# 13-MT7688AN_Peripheral-C.net
KiCad netlist of a schematic drawn in Altium Designer
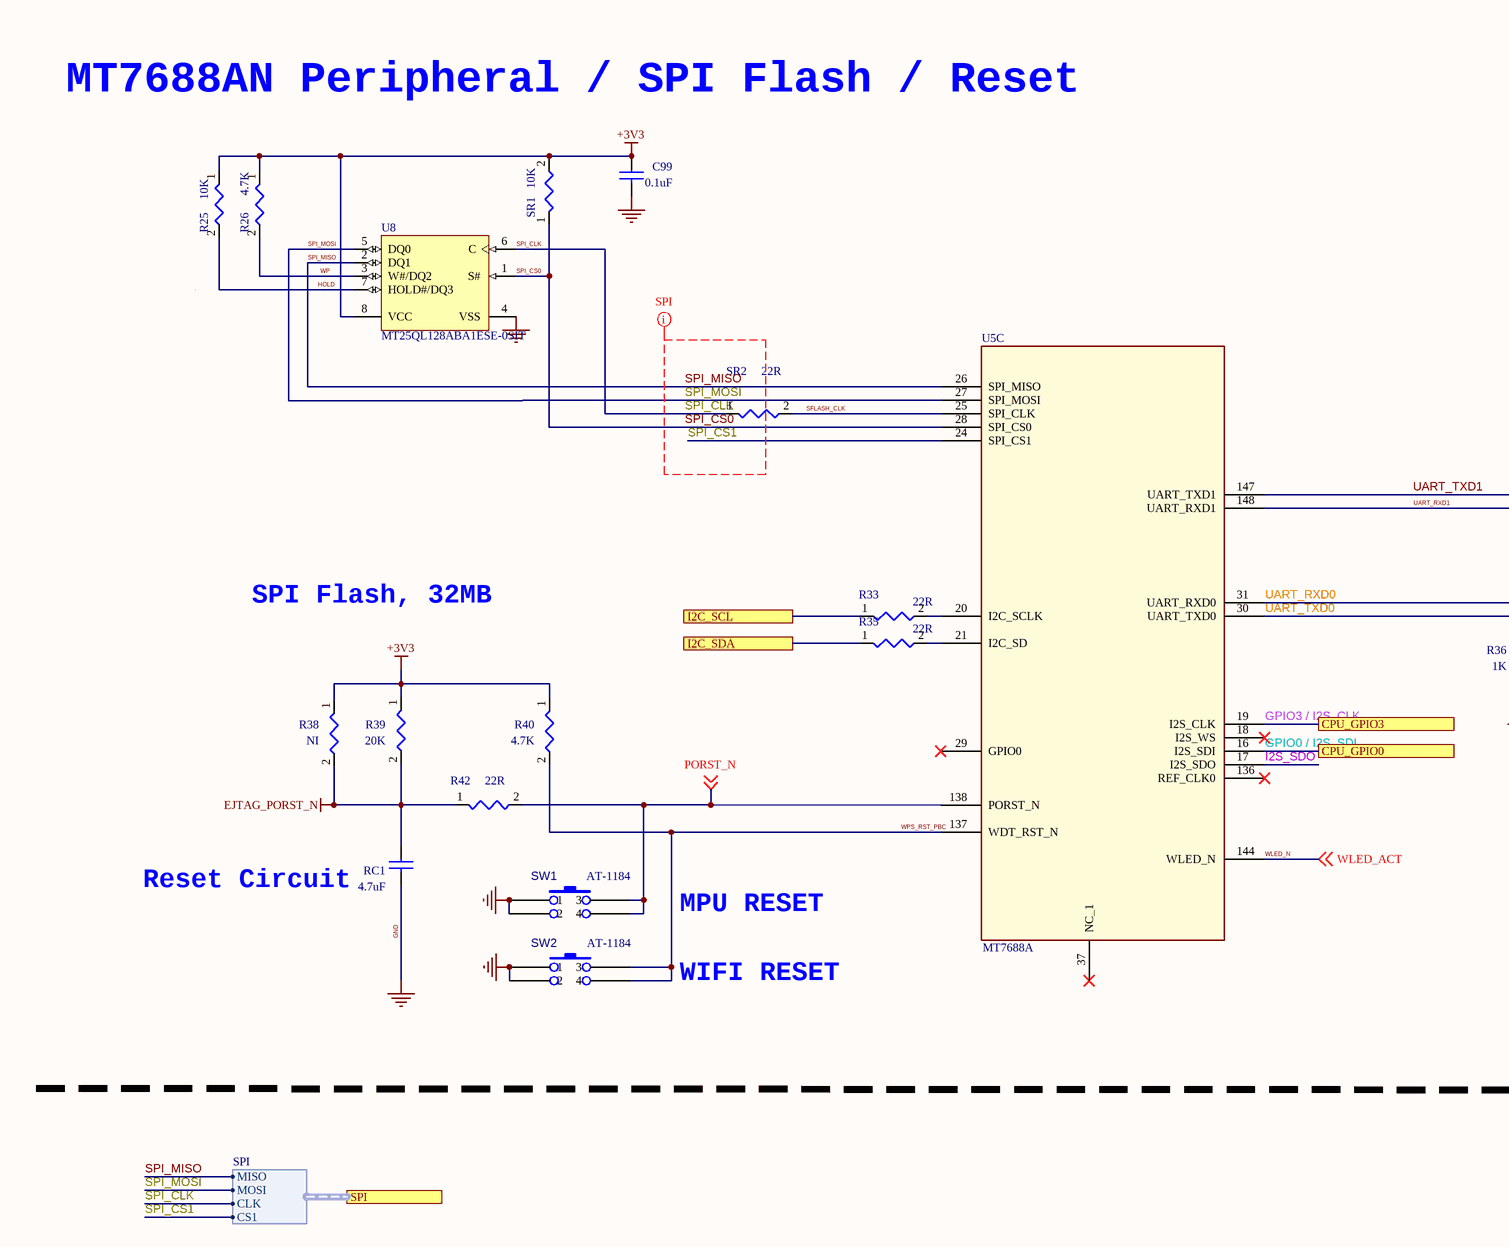
[diagram p0: 13-MT7688AN Peripheral-C.SchDoc, top left]
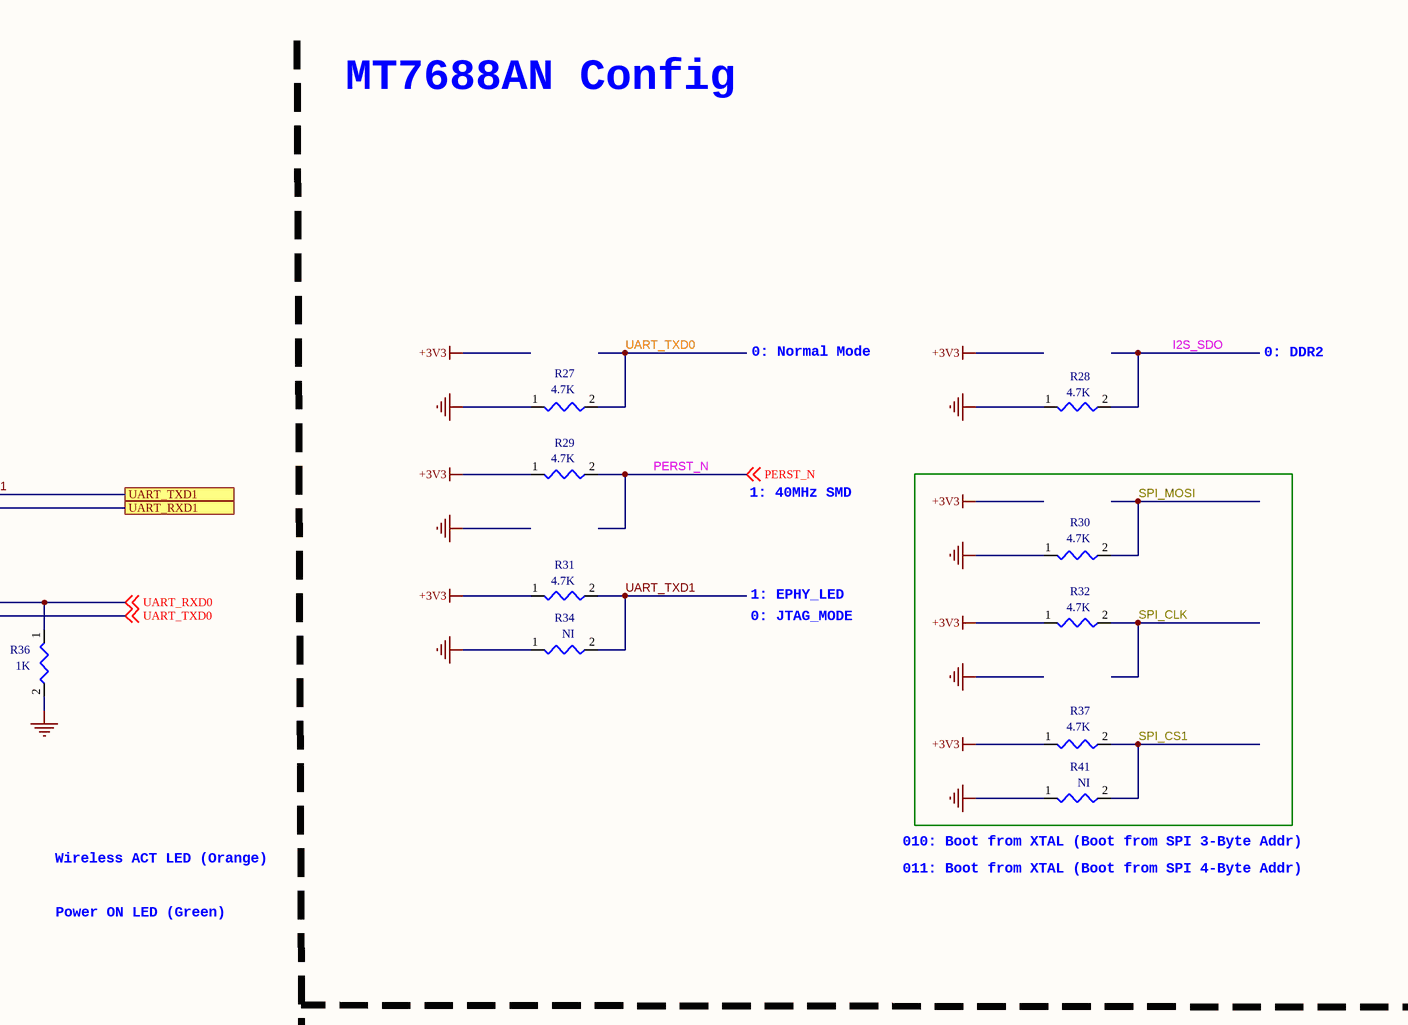
[diagram p1: 13-MT7688AN Peripheral-C.SchDoc, top right]
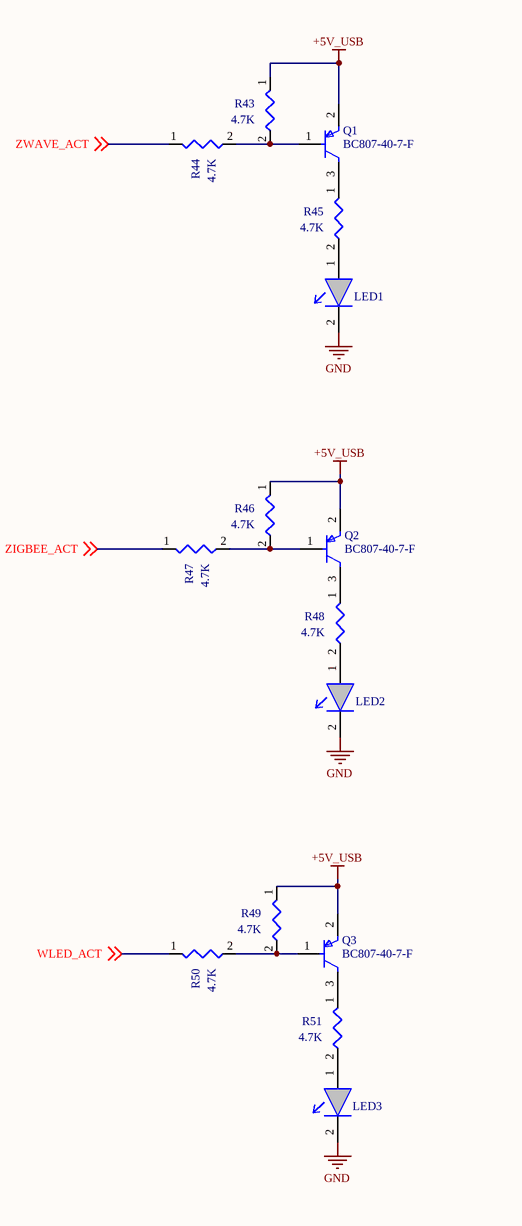
[diagram p2: 13-MT7688AN Peripheral-C.SchDoc, bottom left]
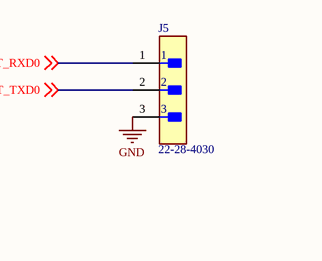
[diagram p3: 13-MT7688AN Peripheral-C.SchDoc, bottom right]

(export (version "E")
  (design (tool "Eeschema 10.0.6"))
  (components
    (comp (ref "C99")
      (value "0.1uF")
      (footprint "CAPC1005X60X30NL05T10")
      (libsource (lib "MT7688AN") (part "CAP NP"))
    )
    (comp (ref "J5")
      (value "22-28-4030")
      (footprint "FP-22-28-4030-MFG")
      (description "CONN HEADER VERT 3POS 2.54MM")
      (fields
        (field (name "OCTOPART") "https://octopart.com/0022284030-molex-10476094")
        (field (name "MANUFACTURER") "Molex")
      )
      (libsource (lib "Altium Content Vault") (part "0d3f023dd272f625e17a2be33dea85f"))
    )
    (comp (ref "LED1")
      (value "LED 2P")
      (footprint "LED3MM 2P")
      (libsource (lib "SyTungNguyen") (part "LED 2P"))
    )
    (comp (ref "LED2")
      (value "LED 2P")
      (footprint "LED3MM 2P")
      (libsource (lib "SyTungNguyen") (part "LED 2P"))
    )
    (comp (ref "LED3")
      (value "LED 2P")
      (footprint "LED3MM 2P")
      (libsource (lib "SyTungNguyen") (part "LED 2P"))
    )
    (comp (ref "Q1")
      (value "BC807-40-7-F")
      (footprint "FP-SOT23-MFG")
      (description "TRANS PNP 45V 0.5A SOT23")
      (fields
        (field (name "OCTOPART") "https://octopart.com/bc807-40-7-f-diodes+inc.-354302")
        (field (name "MANUFACTURER") "DIODES INC.")
      )
      (libsource (lib "Altium Content Vault") (part "0e8486ed3b47d9c69b8404ba87cf0f7"))
    )
    (comp (ref "Q2")
      (value "BC807-40-7-F")
      (footprint "FP-SOT23-MFG")
      (description "TRANS PNP 45V 0.5A SOT23")
      (fields
        (field (name "OCTOPART") "https://octopart.com/bc807-40-7-f-diodes+inc.-354302")
        (field (name "MANUFACTURER") "DIODES INC.")
      )
      (libsource (lib "Altium Content Vault") (part "0e8486ed3b47d9c69b8404ba87cf0f7"))
    )
    (comp (ref "Q3")
      (value "BC807-40-7-F")
      (footprint "FP-SOT23-MFG")
      (description "TRANS PNP 45V 0.5A SOT23")
      (fields
        (field (name "OCTOPART") "https://octopart.com/bc807-40-7-f-diodes+inc.-354302")
        (field (name "MANUFACTURER") "DIODES INC.")
      )
      (libsource (lib "Altium Content Vault") (part "0e8486ed3b47d9c69b8404ba87cf0f7"))
    )
    (comp (ref "R25")
      (value "10K")
      (footprint "RESC1005X35X25NL10T10")
      (libsource (lib "MT7688AN") (part "RES/0402_3"))
    )
    (comp (ref "R26")
      (value "4.7K")
      (footprint "RESC1005X35X25NL10T10")
      (libsource (lib "MT7688AN") (part "RES/0402_3"))
    )
    (comp (ref "R27")
      (value "4.7K")
      (footprint "RESC1005X35X25NL10T10")
      (libsource (lib "MT7688AN") (part "RES/0402_3"))
    )
    (comp (ref "R28")
      (value "4.7K")
      (footprint "RESC1005X35X25NL10T10")
      (libsource (lib "MT7688AN") (part "RES/0402_3"))
    )
    (comp (ref "R29")
      (value "4.7K")
      (footprint "RESC1005X35X25NL10T10")
      (libsource (lib "MT7688AN") (part "RES/0402_3"))
    )
    (comp (ref "R30")
      (value "4.7K")
      (footprint "RESC1005X35X25NL10T10")
      (libsource (lib "MT7688AN") (part "RES/0402_3"))
    )
    (comp (ref "R31")
      (value "4.7K")
      (footprint "RESC1005X35X25NL10T10")
      (libsource (lib "MT7688AN") (part "RES/0402_3"))
    )
    (comp (ref "R32")
      (value "4.7K")
      (footprint "RESC1005X35X25NL10T10")
      (libsource (lib "MT7688AN") (part "RES/0402_3"))
    )
    (comp (ref "R33")
      (value "22R")
      (footprint "RESC1005X35X25NL10T10")
      (libsource (lib "MT7688AN") (part "RES/0402_3"))
    )
    (comp (ref "R34")
      (value "NI")
      (footprint "RESC1005X35X25NL10T10")
      (libsource (lib "MT7688AN") (part "RES/0402_3"))
    )
    (comp (ref "R35")
      (value "22R")
      (footprint "RESC1005X35X25NL10T10")
      (libsource (lib "MT7688AN") (part "RES/0402_3"))
    )
    (comp (ref "R36")
      (value "1K")
      (footprint "RESC1005X35X25NL10T10")
      (libsource (lib "MT7688AN") (part "RES/0402_3"))
    )
    (comp (ref "R37")
      (value "4.7K")
      (footprint "RESC1005X35X25NL10T10")
      (libsource (lib "MT7688AN") (part "RES/0402_3"))
    )
    (comp (ref "R38")
      (value "NI")
      (footprint "RESC1005X35X25NL10T10")
      (libsource (lib "MT7688AN") (part "RES/0402_3"))
    )
    (comp (ref "R39")
      (value "20K")
      (footprint "RESC1005X35X25NL10T10")
      (libsource (lib "MT7688AN") (part "RES/0402_3"))
    )
    (comp (ref "R40")
      (value "4.7K")
      (footprint "RESC1005X35X25NL10T10")
      (libsource (lib "MT7688AN") (part "RES/0402_3"))
    )
    (comp (ref "R41")
      (value "NI")
      (footprint "RESC1005X35X25NL10T10")
      (libsource (lib "MT7688AN") (part "RES/0402_3"))
    )
    (comp (ref "R42")
      (value "22R")
      (footprint "RESC1005X35X25NL10T10")
      (libsource (lib "MT7688AN") (part "RES/0402_3"))
    )
    (comp (ref "R43")
      (value "4.7K")
      (footprint "RESC1005X35X25NL10T10")
      (libsource (lib "MT7688AN") (part "RES/0402_3"))
    )
    (comp (ref "R44")
      (value "4.7K")
      (footprint "RESC1005X35X25NL10T10")
      (libsource (lib "MT7688AN") (part "RES/0402_3"))
    )
    (comp (ref "R45")
      (value "4.7K")
      (footprint "RESC1609X50X30NL10T20")
      (libsource (lib "MT7688AN") (part "RES/0402_3"))
    )
    (comp (ref "R46")
      (value "4.7K")
      (footprint "RESC1005X35X25NL10T10")
      (libsource (lib "MT7688AN") (part "RES/0402_3"))
    )
    (comp (ref "R47")
      (value "4.7K")
      (footprint "RESC1005X35X25NL10T10")
      (libsource (lib "MT7688AN") (part "RES/0402_3"))
    )
    (comp (ref "R48")
      (value "4.7K")
      (footprint "RESC1609X50X30NL10T20")
      (libsource (lib "MT7688AN") (part "RES/0402_3"))
    )
    (comp (ref "R49")
      (value "4.7K")
      (footprint "RESC1005X35X25NL10T10")
      (libsource (lib "MT7688AN") (part "RES/0402_3"))
    )
    (comp (ref "R50")
      (value "4.7K")
      (footprint "RESC1005X35X25NL10T10")
      (libsource (lib "MT7688AN") (part "RES/0402_3"))
    )
    (comp (ref "R51")
      (value "4.7K")
      (footprint "RESC1609X50X30NL10T20")
      (libsource (lib "MT7688AN") (part "RES/0402_3"))
    )
    (comp (ref "RC1")
      (value "4.7uF")
      (footprint "CAPC1005X60X30NL05T10")
      (libsource (lib "MT7688AN") (part "CAP NP"))
    )
    (comp (ref "SR1")
      (value "10K")
      (footprint "RESC1005X35X25NL10T10")
      (libsource (lib "MT7688AN") (part "RES/0402_3"))
    )
    (comp (ref "SR2")
      (value "22R")
      (footprint "RESC1005X35X25NL10T10")
      (libsource (lib "MT7688AN") (part "RES/0402_3"))
    )
    (comp (ref "SW1")
      (value "AT-1184")
      (footprint "AT-1184 SW")
      (description "TACT Switch, H=1.5mm")
      (fields (field (name "MANUFACTURER") "Panasonic - ECG"))
      (libsource (lib "MT7688AN") (part "SW"))
    )
    (comp (ref "SW2")
      (value "AT-1184")
      (footprint "AT-1184 SW")
      (description "TACT Switch, H=1.5mm")
      (fields (field (name "MANUFACTURER") "Panasonic - ECG"))
      (libsource (lib "MT7688AN") (part "SW"))
    )
    (comp (ref "U5")
      (value "MT7688A")
      (footprint "MT7628AN$2F$DRQFN156$2F$SMD$2F$P0.5$2F$12X12")
      (libsource (lib "MT7688AN") (part "MT7620N-n_26"))
    )
    (comp (ref "U8")
      (value "MT25QL128ABA1ESE-0SIT")
      (footprint "SOIC8_N")
      (fields (field (name "MANUFACTURER") "Micron"))
      (libsource (lib "HAGateWay202205V10") (part "MICT-MT25QL128ABA-SOP2-8"))
    )
  )
  (nets
    (net (code "2") (name "+3V3") (class "Default")
      (node (ref "C99") (pin "1") (pinfunction "1_1") (pintype "passive"))
      (node (ref "R25") (pin "1") (pinfunction "1_1") (pintype "passive"))
      (node (ref "R26") (pin "1") (pinfunction "1_1") (pintype "passive"))
      (node (ref "R29") (pin "1") (pinfunction "1_1") (pintype "passive"))
      (node (ref "R31") (pin "1") (pinfunction "1_1") (pintype "passive"))
      (node (ref "R32") (pin "1") (pinfunction "1_1") (pintype "passive"))
      (node (ref "R37") (pin "1") (pinfunction "1_1") (pintype "passive"))
      (node (ref "R38") (pin "1") (pinfunction "1_1") (pintype "passive"))
      (node (ref "R39") (pin "1") (pinfunction "1_1") (pintype "passive"))
      (node (ref "R40") (pin "1") (pinfunction "1_1") (pintype "passive"))
      (node (ref "SR1") (pin "2") (pinfunction "2_2") (pintype "passive"))
      (node (ref "U8") (pin "8") (pinfunction "VCC_8") (pintype "power_in"))
    )
    (net (code "3") (name "+5V_USB") (class "Default")
      (node (ref "Q1") (pin "2") (pinfunction "E_2") (pintype "passive"))
      (node (ref "Q2") (pin "2") (pinfunction "E_2") (pintype "passive"))
      (node (ref "Q3") (pin "2") (pinfunction "E_2") (pintype "passive"))
      (node (ref "R43") (pin "1") (pinfunction "1_1") (pintype "passive"))
      (node (ref "R46") (pin "1") (pinfunction "1_1") (pintype "passive"))
      (node (ref "R49") (pin "1") (pinfunction "1_1") (pintype "passive"))
    )
    (net (code "4") (name "/GPIO0 {slash} I2S_SDI") (class "Default")
      (node (ref "U5") (pin "16") (pinfunction "I2S_SDI_16") (pintype "passive"))
    )
    (net (code "5") (name "/GPIO3 {slash} I2S_CLK") (class "Default")
      (node (ref "U5") (pin "19") (pinfunction "I2S_CLK_19") (pintype "passive"))
    )
    (net (code "6") (name "/HOLD") (class "Default")
      (node (ref "R25") (pin "2") (pinfunction "2_2") (pintype "passive"))
      (node (ref "U8") (pin "7") (pinfunction "HOLD#/DQ3_7") (pintype "bidirectional"))
    )
    (net (code "7") (name "/I2C_SCL") (class "Default")
      (node (ref "R33") (pin "1") (pinfunction "1_1") (pintype "passive"))
    )
    (net (code "8") (name "/I2C_SDA") (class "Default")
      (node (ref "R35") (pin "1") (pinfunction "1_1") (pintype "passive"))
    )
    (net (code "9") (name "/I2S_SDO") (class "Default")
      (node (ref "R28") (pin "2") (pinfunction "2_2") (pintype "passive"))
      (node (ref "U5") (pin "17") (pinfunction "I2S_SDO_17") (pintype "passive"))
    )
    (net (code "10") (name "/SFLASH_CLK") (class "Default")
      (node (ref "SR2") (pin "2") (pinfunction "2_2") (pintype "passive"))
      (node (ref "U5") (pin "25") (pinfunction "SPI_CLK_25") (pintype "passive"))
    )
    (net (code "11") (name "/SPI_CLK") (class "Default")
      (node (ref "R32") (pin "2") (pinfunction "2_2") (pintype "passive"))
      (node (ref "SR2") (pin "1") (pinfunction "1_1") (pintype "passive"))
      (node (ref "U8") (pin "6") (pinfunction "C_6") (pintype "input"))
    )
    (net (code "12") (name "/SPI_CS0") (class "Default")
      (node (ref "SR1") (pin "1") (pinfunction "1_1") (pintype "passive"))
      (node (ref "U5") (pin "28") (pinfunction "SPI_CS0_28") (pintype "passive"))
      (node (ref "U8") (pin "1") (pinfunction "S#_1") (pintype "input"))
    )
    (net (code "13") (name "/SPI_CS1") (class "Default")
      (node (ref "R37") (pin "2") (pinfunction "2_2") (pintype "passive"))
      (node (ref "R41") (pin "2") (pinfunction "2_2") (pintype "passive"))
      (node (ref "U5") (pin "24") (pinfunction "SPI_CS1_24") (pintype "passive"))
    )
    (net (code "14") (name "/SPI_MISO") (class "Default")
      (node (ref "U5") (pin "26") (pinfunction "SPI_MISO_26") (pintype "passive"))
      (node (ref "U8") (pin "2") (pinfunction "DQ1_2") (pintype "bidirectional"))
    )
    (net (code "15") (name "/SPI_MOSI") (class "Default")
      (node (ref "R30") (pin "2") (pinfunction "2_2") (pintype "passive"))
      (node (ref "U5") (pin "27") (pinfunction "SPI_MOSI_27") (pintype "passive"))
      (node (ref "U8") (pin "5") (pinfunction "DQ0_5") (pintype "bidirectional"))
    )
    (net (code "16") (name "/UART_RXD1") (class "Default")
      (node (ref "U5") (pin "148") (pinfunction "UART_RXD1_148") (pintype "passive"))
    )
    (net (code "17") (name "/UART_TXD1") (class "Default")
      (node (ref "R31") (pin "2") (pinfunction "2_2") (pintype "passive"))
      (node (ref "R34") (pin "2") (pinfunction "2_2") (pintype "passive"))
      (node (ref "U5") (pin "147") (pinfunction "UART_TXD1_147") (pintype "passive"))
    )
    (net (code "18") (name "/WP") (class "Default")
      (node (ref "R26") (pin "2") (pinfunction "2_2") (pintype "passive"))
      (node (ref "U8") (pin "3") (pinfunction "W#/DQ2_3") (pintype "bidirectional"))
    )
    (net (code "19") (name "/WPS_RST_PBC") (class "Default")
      (node (ref "R40") (pin "2") (pinfunction "2_2") (pintype "passive"))
      (node (ref "SW2") (pin "3") (pinfunction "3_3") (pintype "passive"))
      (node (ref "SW2") (pin "4") (pinfunction "4_4") (pintype "passive"))
      (node (ref "U5") (pin "137") (pinfunction "WDT_RST_N_137") (pintype "passive"))
    )
    (net (code "21") (name "EJTAG_PORST_N") (class "Default")
      (node (ref "R38") (pin "2") (pinfunction "2_2") (pintype "passive"))
      (node (ref "R39") (pin "2") (pinfunction "2_2") (pintype "passive"))
      (node (ref "R42") (pin "1") (pinfunction "1_1") (pintype "passive"))
      (node (ref "RC1") (pin "1") (pinfunction "1_1") (pintype "passive"))
    )
    (net (code "22") (name "GND") (class "Default")
      (node (ref "C99") (pin "2") (pinfunction "2_2") (pintype "passive"))
      (node (ref "J5") (pin "3") (pinfunction "3_3") (pintype "passive"))
      (node (ref "LED1") (pin "2") (pinfunction "2_2") (pintype "passive"))
      (node (ref "LED2") (pin "2") (pinfunction "2_2") (pintype "passive"))
      (node (ref "LED3") (pin "2") (pinfunction "2_2") (pintype "passive"))
      (node (ref "R27") (pin "1") (pinfunction "1_1") (pintype "passive"))
      (node (ref "R28") (pin "1") (pinfunction "1_1") (pintype "passive"))
      (node (ref "R30") (pin "1") (pinfunction "1_1") (pintype "passive"))
      (node (ref "R34") (pin "1") (pinfunction "1_1") (pintype "passive"))
      (node (ref "R36") (pin "2") (pinfunction "2_2") (pintype "passive"))
      (node (ref "R41") (pin "1") (pinfunction "1_1") (pintype "passive"))
      (node (ref "RC1") (pin "2") (pinfunction "2_2") (pintype "passive"))
      (node (ref "SW1") (pin "1") (pinfunction "1_1") (pintype "passive"))
      (node (ref "SW1") (pin "2") (pinfunction "2_2") (pintype "passive"))
      (node (ref "SW2") (pin "1") (pinfunction "1_1") (pintype "passive"))
      (node (ref "SW2") (pin "2") (pinfunction "2_2") (pintype "passive"))
      (node (ref "U8") (pin "4") (pinfunction "VSS_4") (pintype "power_in"))
    )
    (net (code "23") (name "Net-(LED1-Pad1)") (class "Default")
      (node (ref "LED1") (pin "1") (pinfunction "1_1") (pintype "passive"))
      (node (ref "R45") (pin "2") (pinfunction "2_2") (pintype "passive"))
    )
    (net (code "24") (name "Net-(LED2-Pad1)") (class "Default")
      (node (ref "LED2") (pin "1") (pinfunction "1_1") (pintype "passive"))
      (node (ref "R48") (pin "2") (pinfunction "2_2") (pintype "passive"))
    )
    (net (code "25") (name "Net-(LED3-Pad1)") (class "Default")
      (node (ref "LED3") (pin "1") (pinfunction "1_1") (pintype "passive"))
      (node (ref "R51") (pin "2") (pinfunction "2_2") (pintype "passive"))
    )
    (net (code "26") (name "Net-(Q1-B)") (class "Default")
      (node (ref "Q1") (pin "1") (pinfunction "B_1") (pintype "passive"))
      (node (ref "R43") (pin "2") (pinfunction "2_2") (pintype "passive"))
      (node (ref "R44") (pin "2") (pinfunction "2_2") (pintype "passive"))
    )
    (net (code "27") (name "Net-(Q1-C)") (class "Default")
      (node (ref "Q1") (pin "3") (pinfunction "C_3") (pintype "passive"))
      (node (ref "R45") (pin "1") (pinfunction "1_1") (pintype "passive"))
    )
    (net (code "28") (name "Net-(Q2-B)") (class "Default")
      (node (ref "Q2") (pin "1") (pinfunction "B_1") (pintype "passive"))
      (node (ref "R46") (pin "2") (pinfunction "2_2") (pintype "passive"))
      (node (ref "R47") (pin "2") (pinfunction "2_2") (pintype "passive"))
    )
    (net (code "29") (name "Net-(Q2-C)") (class "Default")
      (node (ref "Q2") (pin "3") (pinfunction "C_3") (pintype "passive"))
      (node (ref "R48") (pin "1") (pinfunction "1_1") (pintype "passive"))
    )
    (net (code "30") (name "Net-(Q3-B)") (class "Default")
      (node (ref "Q3") (pin "1") (pinfunction "B_1") (pintype "passive"))
      (node (ref "R49") (pin "2") (pinfunction "2_2") (pintype "passive"))
      (node (ref "R50") (pin "2") (pinfunction "2_2") (pintype "passive"))
    )
    (net (code "31") (name "Net-(Q3-C)") (class "Default")
      (node (ref "Q3") (pin "3") (pinfunction "C_3") (pintype "passive"))
      (node (ref "R51") (pin "1") (pinfunction "1_1") (pintype "passive"))
    )
    (net (code "32") (name "Net-(U5C-I2C_SCLK)") (class "Default")
      (node (ref "R33") (pin "2") (pinfunction "2_2") (pintype "passive"))
      (node (ref "U5") (pin "20") (pinfunction "I2C_SCLK_20") (pintype "passive"))
    )
    (net (code "33") (name "Net-(U5C-I2C_SD)") (class "Default")
      (node (ref "R35") (pin "2") (pinfunction "2_2") (pintype "passive"))
      (node (ref "U5") (pin "21") (pinfunction "I2C_SD_21") (pintype "passive"))
    )
    (net (code "34") (name "PERST_N") (class "Default")
      (node (ref "R29") (pin "2") (pinfunction "2_2") (pintype "passive"))
    )
    (net (code "35") (name "PORST_N") (class "Default")
      (node (ref "R42") (pin "2") (pinfunction "2_2") (pintype "passive"))
      (node (ref "SW1") (pin "3") (pinfunction "3_3") (pintype "passive"))
      (node (ref "SW1") (pin "4") (pinfunction "4_4") (pintype "passive"))
      (node (ref "U5") (pin "138") (pinfunction "PORST_N_138") (pintype "passive"))
    )
    (net (code "36") (name "UART_RXD0") (class "Default")
      (node (ref "J5") (pin "1") (pinfunction "1_1") (pintype "passive"))
      (node (ref "R36") (pin "1") (pinfunction "1_1") (pintype "passive"))
      (node (ref "U5") (pin "31") (pinfunction "UART_RXD0_31") (pintype "passive"))
    )
    (net (code "37") (name "UART_TXD0") (class "Default")
      (node (ref "J5") (pin "2") (pinfunction "2_2") (pintype "passive"))
      (node (ref "R27") (pin "2") (pinfunction "2_2") (pintype "passive"))
      (node (ref "U5") (pin "30") (pinfunction "UART_TXD0_30") (pintype "passive"))
    )
    (net (code "38") (name "WLED_ACT") (class "Default")
      (node (ref "R50") (pin "1") (pinfunction "1_1") (pintype "passive"))
      (node (ref "U5") (pin "144") (pinfunction "WLED_N_144") (pintype "passive"))
    )
    (net (code "39") (name "ZIGBEE_ACT") (class "Default")
      (node (ref "R47") (pin "1") (pinfunction "1_1") (pintype "passive"))
    )
    (net (code "40") (name "ZWAVE_ACT") (class "Default")
      (node (ref "R44") (pin "1") (pinfunction "1_1") (pintype "passive"))
    )
    (net (code "41") (name "unconnected-(U5C-GPIO0-Pad29)") (class "Default")
      (node (ref "U5") (pin "29") (pinfunction "GPIO0_29") (pintype "passive+no_connect"))
    )
    (net (code "42") (name "unconnected-(U5C-I2S_WS-Pad18)") (class "Default")
      (node (ref "U5") (pin "18") (pinfunction "I2S_WS_18") (pintype "passive+no_connect"))
    )
    (net (code "43") (name "unconnected-(U5C-NC_1-Pad37)") (class "Default")
      (node (ref "U5") (pin "37") (pinfunction "NC_1_37") (pintype "passive+no_connect"))
    )
    (net (code "44") (name "unconnected-(U5C-REF_CLK0-Pad136)") (class "Default")
      (node (ref "U5") (pin "136") (pinfunction "REF_CLK0_136") (pintype "passive+no_connect"))
    )
  )
)
